# config.net
KiCad netlist of a schematic drawn in Altium Designer
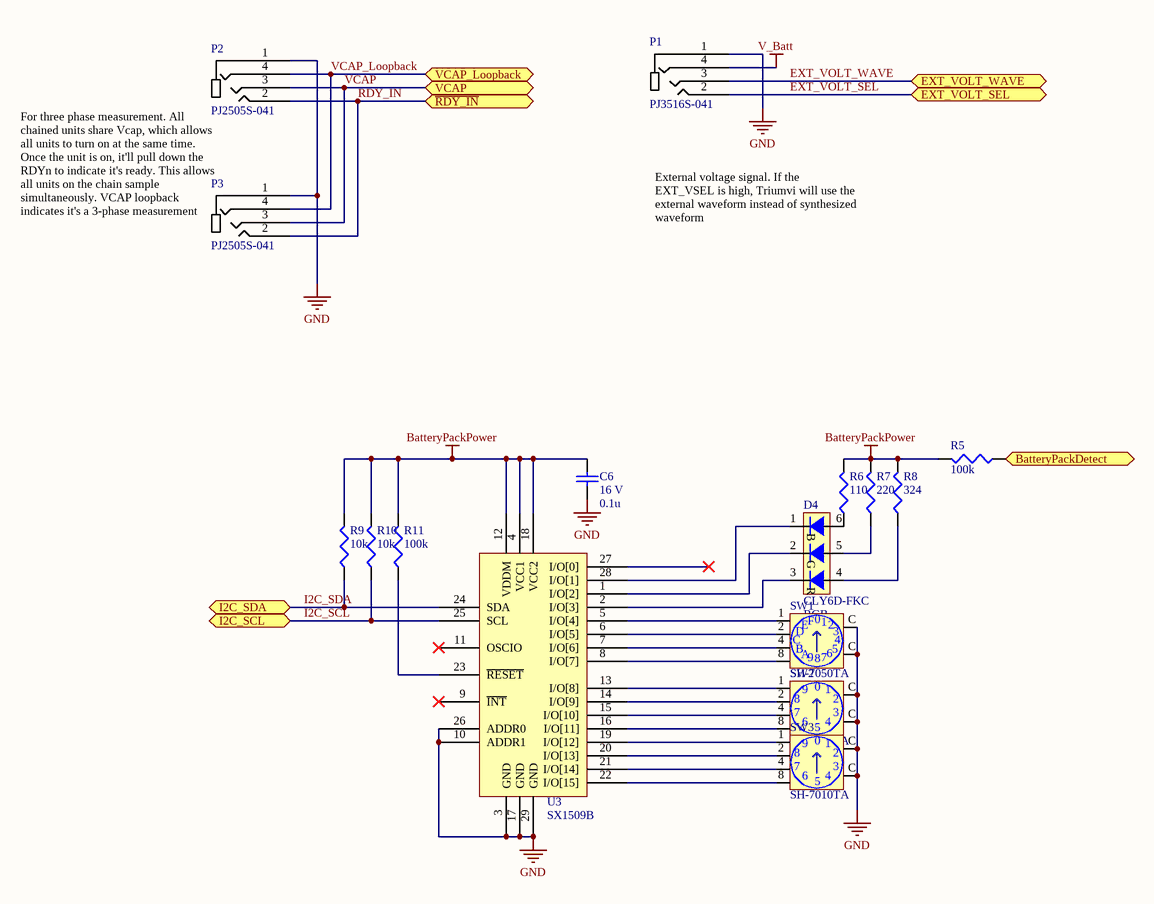
[diagram p0: config.SchDoc]

(export (version "E")
  (design (tool "Eeschema 10.0.6"))
  (components
    (comp (ref "C6")
      (value "0.1u")
      (footprint "0402")
      (description "0.10µF ±10% 16V Ceramic Capacitor X7R 0402")
      (fields
        (field (name "VOLTAGE RATED") "16 V")
        (field (name "TOLERANCE") "10%")
        (field (name "MANUFACTURER PART NUMBER") "GRM155R71C104KA88D")
      )
      (libsource (lib "capacitors") (part "GRM155R71C104KA88D"))
    )
    (comp (ref "D4")
      (value "CLY6D-FKC")
      (footprint "PLCC6")
      (fields
        (field (name "MANUFACTURER PART NUMBER") "CLY6D-FKC-CK1N1D1BB7D3D3")
        (field (name "MANUFACTURER") "CREE Inc")
        (field (name "ALTIUM_VALUE") "RGB")
      )
      (libsource (lib "LED") (part "CLY6D-FKC-CK1N1D1BB7D3D3"))
    )
    (comp (ref "P1")
      (value "PJ3516S-041")
      (footprint "PJ3516S-041")
      (description "3.5 mm phone jack, 4 terminals")
      (libsource (lib "connectors") (part "PJ3516S-041"))
    )
    (comp (ref "P2")
      (value "PJ2505S-041")
      (footprint "PJ2505S-041")
      (description "2.5 mm phone jack, 4 terminals")
      (libsource (lib "connectors") (part "PJ2505S-041"))
    )
    (comp (ref "P3")
      (value "PJ2505S-041")
      (footprint "PJ2505S-041")
      (description "2.5 mm phone jack, 4 terminals")
      (libsource (lib "connectors") (part "PJ2505S-041"))
    )
    (comp (ref "R5")
      (value "100k")
      (footprint "0402")
      (description "RES SMD 100K OHM 1% 1/16W 0402")
      (fields (field (name "TOLERANCE") "1%") (field (name "POWER") "1/16 W"))
      (libsource (lib "resistors") (part "CRCW0402100KFKED"))
    )
    (comp (ref "R6")
      (value "110")
      (footprint "0402")
      (description "RES SMD 110 OHM 1% 1/16W 0402")
      (fields (field (name "TOLERANCE") "1%") (field (name "POWER") "1/16 W"))
      (libsource (lib "resistors") (part "CRCW0402110RFKED"))
    )
    (comp (ref "R7")
      (value "220")
      (footprint "0402")
      (description "RES SMD 220 OHM 1% 1/16W 0402")
      (fields (field (name "TOLERANCE") "1%") (field (name "POWER") "1/5 W"))
      (libsource (lib "resistors") (part "CRCW0402220RFKED"))
    )
    (comp (ref "R8")
      (value "324")
      (footprint "0402")
      (description "RES SMD 324 OHM 1% 1/16W 0402")
      (fields (field (name "TOLERANCE") "1%") (field (name "POWER") "1/16 W"))
      (libsource (lib "resistors") (part "CRCW0402324RFKED"))
    )
    (comp (ref "R9")
      (value "10k")
      (footprint "0402")
      (description "RES SMD 10K OHM 1% 1/16W 0402")
      (fields (field (name "TOLERANCE") "1%") (field (name "POWER") "1/16 W"))
      (libsource (lib "resistors") (part "CRCW040210K0FKED"))
    )
    (comp (ref "R10")
      (value "10k")
      (footprint "0402")
      (description "RES SMD 10K OHM 1% 1/16W 0402")
      (fields (field (name "TOLERANCE") "1%") (field (name "POWER") "1/16 W"))
      (libsource (lib "resistors") (part "CRCW040210K0FKED"))
    )
    (comp (ref "R11")
      (value "100k")
      (footprint "0402")
      (description "RES SMD 100K OHM 1% 1/16W 0402")
      (fields (field (name "TOLERANCE") "1%") (field (name "POWER") "1/16 W"))
      (libsource (lib "resistors") (part "CRCW0402100KFKED"))
    )
    (comp (ref "SW1")
      (value "SH-7050TA")
      (footprint "SH-7050A")
      (description "ROTARY CODED SWITCHES")
      (libsource (lib "switches") (part "SH-7050TA"))
    )
    (comp (ref "SW2")
      (value "SH-7010TA")
      (footprint "SH-7010A")
      (description "ROTARY CODED SWITCHES")
      (libsource (lib "switches") (part "SH-7010TA"))
    )
    (comp (ref "SW3")
      (value "SH-7010TA")
      (footprint "SH-7010A")
      (description "ROTARY CODED SWITCHES")
      (libsource (lib "switches") (part "SH-7010TA"))
    )
    (comp (ref "U3")
      (value "SX1509B")
      (footprint "QFN40P400X400X60_HS-29N")
      (description "Voltage Level Shifting GPIO  with LED Driver and Keypad Engine")
      (libsource (lib "io expander") (part "SX1509B"))
    )
  )
  (nets
    (net (code "1") (name "/BatteryPackDetect") (class "Default")
      (node (ref "R5") (pin "2") (pintype "passive"))
    )
    (net (code "2") (name "/EXT_VOLT_SEL") (class "Default")
      (node (ref "P1") (pin "2") (pinfunction "2_2") (pintype "passive"))
    )
    (net (code "3") (name "/EXT_VOLT_WAVE") (class "Default")
      (node (ref "P1") (pin "3") (pinfunction "3_3") (pintype "passive"))
    )
    (net (code "4") (name "/I2C_SCL") (class "Default")
      (node (ref "R10") (pin "2") (pintype "passive"))
      (node (ref "U3") (pin "25") (pinfunction "SCL_25") (pintype "passive"))
    )
    (net (code "5") (name "/I2C_SDA") (class "Default")
      (node (ref "R9") (pin "2") (pintype "passive"))
      (node (ref "U3") (pin "24") (pinfunction "SDA_24") (pintype "passive"))
    )
    (net (code "6") (name "/VCAP") (class "Default")
      (node (ref "P2") (pin "3") (pinfunction "3_3") (pintype "passive"))
      (node (ref "P3") (pin "3") (pinfunction "3_3") (pintype "passive"))
    )
    (net (code "7") (name "/VCAP_Loopback") (class "Default")
      (node (ref "P2") (pin "4") (pinfunction "4_4") (pintype "passive"))
      (node (ref "P3") (pin "4") (pinfunction "4_4") (pintype "passive"))
    )
    (net (code "8") (name "/~{RDY_IN}") (class "Default")
      (node (ref "P2") (pin "2") (pinfunction "2_2") (pintype "passive"))
      (node (ref "P3") (pin "2") (pinfunction "2_2") (pintype "passive"))
    )
    (net (code "9") (name "BatteryPackPower") (class "Default")
      (node (ref "C6") (pin "1") (pintype "passive"))
      (node (ref "R10") (pin "1") (pintype "passive"))
      (node (ref "R11") (pin "1") (pintype "passive"))
      (node (ref "R5") (pin "1") (pintype "passive"))
      (node (ref "R6") (pin "1") (pintype "passive"))
      (node (ref "R7") (pin "1") (pintype "passive"))
      (node (ref "R8") (pin "1") (pintype "passive"))
      (node (ref "R9") (pin "1") (pintype "passive"))
      (node (ref "U3") (pin "12") (pinfunction "VDDM_12") (pintype "passive"))
      (node (ref "U3") (pin "18") (pinfunction "VCC2_18") (pintype "passive"))
      (node (ref "U3") (pin "4") (pinfunction "VCC1_4") (pintype "passive"))
    )
    (net (code "10") (name "GND") (class "Default")
      (node (ref "C6") (pin "2") (pintype "passive"))
      (node (ref "P1") (pin "1") (pinfunction "1_1") (pintype "passive"))
      (node (ref "P2") (pin "1") (pinfunction "1_1") (pintype "passive"))
      (node (ref "P3") (pin "1") (pinfunction "1_1") (pintype "passive"))
      (node (ref "SW1") (pin "C") (pinfunction "C_C") (pintype "passive"))
      (node (ref "SW2") (pin "C") (pinfunction "C_C") (pintype "passive"))
      (node (ref "SW3") (pin "C") (pinfunction "C_C") (pintype "passive"))
      (node (ref "U3") (pin "10") (pinfunction "ADDR1_10") (pintype "passive"))
      (node (ref "U3") (pin "17") (pinfunction "GND_17") (pintype "passive"))
      (node (ref "U3") (pin "26") (pinfunction "ADDR0_26") (pintype "passive"))
      (node (ref "U3") (pin "29") (pinfunction "GND_29") (pintype "passive"))
      (node (ref "U3") (pin "3") (pinfunction "GND_3") (pintype "passive"))
    )
    (net (code "11") (name "Net-(D4-Pad4)") (class "Default")
      (node (ref "D4") (pin "4") (pinfunction "4_4") (pintype "passive"))
      (node (ref "R8") (pin "2") (pintype "passive"))
    )
    (net (code "12") (name "Net-(D4-Pad5)") (class "Default")
      (node (ref "D4") (pin "5") (pinfunction "5_5") (pintype "passive"))
      (node (ref "R7") (pin "2") (pintype "passive"))
    )
    (net (code "13") (name "Net-(D4-Pad6)") (class "Default")
      (node (ref "D4") (pin "6") (pinfunction "6_6") (pintype "passive"))
      (node (ref "R6") (pin "2") (pintype "passive"))
    )
    (net (code "14") (name "Net-(U3-I{slash}O[1])") (class "Default")
      (node (ref "D4") (pin "1") (pintype "passive"))
      (node (ref "U3") (pin "28") (pinfunction "I/O[1]_28") (pintype "passive"))
    )
    (net (code "15") (name "Net-(U3-I{slash}O[2])") (class "Default")
      (node (ref "D4") (pin "2") (pintype "passive"))
      (node (ref "U3") (pin "1") (pinfunction "I/O[2]_1") (pintype "passive"))
    )
    (net (code "16") (name "Net-(U3-I{slash}O[3])") (class "Default")
      (node (ref "D4") (pin "3") (pinfunction "3_3") (pintype "passive"))
      (node (ref "U3") (pin "2") (pinfunction "I/O[3]_2") (pintype "passive"))
    )
    (net (code "17") (name "Net-(U3-I{slash}O[4])") (class "Default")
      (node (ref "SW1") (pin "1") (pinfunction "1_1") (pintype "passive"))
      (node (ref "U3") (pin "5") (pinfunction "I/O[4]_5") (pintype "passive"))
    )
    (net (code "18") (name "Net-(U3-I{slash}O[5])") (class "Default")
      (node (ref "SW1") (pin "2") (pinfunction "2_2") (pintype "passive"))
      (node (ref "U3") (pin "6") (pinfunction "I/O[5]_6") (pintype "passive"))
    )
    (net (code "19") (name "Net-(U3-I{slash}O[6])") (class "Default")
      (node (ref "SW1") (pin "4") (pinfunction "4_4") (pintype "passive"))
      (node (ref "U3") (pin "7") (pinfunction "I/O[6]_7") (pintype "passive"))
    )
    (net (code "20") (name "Net-(U3-I{slash}O[7])") (class "Default")
      (node (ref "SW1") (pin "8") (pinfunction "8_8") (pintype "passive"))
      (node (ref "U3") (pin "8") (pinfunction "I/O[7]_8") (pintype "passive"))
    )
    (net (code "21") (name "Net-(U3-I{slash}O[8])") (class "Default")
      (node (ref "SW2") (pin "1") (pinfunction "1_1") (pintype "passive"))
      (node (ref "U3") (pin "13") (pinfunction "I/O[8]_13") (pintype "passive"))
    )
    (net (code "22") (name "Net-(U3-I{slash}O[9])") (class "Default")
      (node (ref "SW2") (pin "2") (pinfunction "2_2") (pintype "passive"))
      (node (ref "U3") (pin "14") (pinfunction "I/O[9]_14") (pintype "passive"))
    )
    (net (code "23") (name "Net-(U3-I{slash}O[10])") (class "Default")
      (node (ref "SW2") (pin "4") (pinfunction "4_4") (pintype "passive"))
      (node (ref "U3") (pin "15") (pinfunction "I/O[10]_15") (pintype "passive"))
    )
    (net (code "24") (name "Net-(U3-I{slash}O[11])") (class "Default")
      (node (ref "SW2") (pin "8") (pinfunction "8_8") (pintype "passive"))
      (node (ref "U3") (pin "16") (pinfunction "I/O[11]_16") (pintype "passive"))
    )
    (net (code "25") (name "Net-(U3-I{slash}O[12])") (class "Default")
      (node (ref "SW3") (pin "1") (pinfunction "1_1") (pintype "passive"))
      (node (ref "U3") (pin "19") (pinfunction "I/O[12]_19") (pintype "passive"))
    )
    (net (code "26") (name "Net-(U3-I{slash}O[13])") (class "Default")
      (node (ref "SW3") (pin "2") (pinfunction "2_2") (pintype "passive"))
      (node (ref "U3") (pin "20") (pinfunction "I/O[13]_20") (pintype "passive"))
    )
    (net (code "27") (name "Net-(U3-I{slash}O[14])") (class "Default")
      (node (ref "SW3") (pin "4") (pinfunction "4_4") (pintype "passive"))
      (node (ref "U3") (pin "21") (pinfunction "I/O[14]_21") (pintype "passive"))
    )
    (net (code "28") (name "Net-(U3-I{slash}O[15])") (class "Default")
      (node (ref "SW3") (pin "8") (pinfunction "8_8") (pintype "passive"))
      (node (ref "U3") (pin "22") (pinfunction "I/O[15]_22") (pintype "passive"))
    )
    (net (code "29") (name "Net-(U3-~{RESET})") (class "Default")
      (node (ref "R11") (pin "2") (pintype "passive"))
      (node (ref "U3") (pin "23") (pinfunction "~{RESET}_23") (pintype "passive"))
    )
    (net (code "30") (name "V_Batt") (class "Default")
      (node (ref "P1") (pin "4") (pinfunction "4_4") (pintype "passive"))
    )
    (net (code "31") (name "unconnected-(U3-I{slash}O[0]-Pad27)") (class "Default")
      (node (ref "U3") (pin "27") (pinfunction "I/O[0]_27") (pintype "passive+no_connect"))
    )
    (net (code "32") (name "unconnected-(U3-OSCIO-Pad11)") (class "Default")
      (node (ref "U3") (pin "11") (pinfunction "OSCIO_11") (pintype "passive+no_connect"))
    )
    (net (code "33") (name "unconnected-(U3-~{INT}-Pad9)") (class "Default")
      (node (ref "U3") (pin "9") (pinfunction "~{INT}_9") (pintype "passive+no_connect"))
    )
  )
)
